# Pwr_entry.net
KiCad netlist of a schematic drawn in Altium Designer
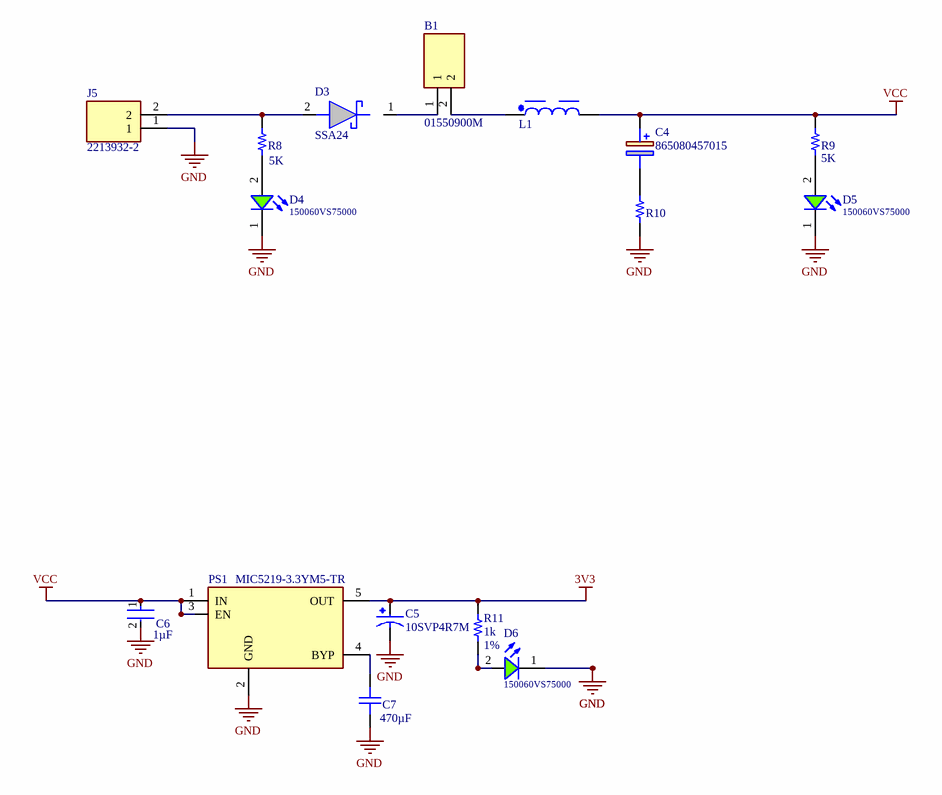
[diagram p0: Pwr_entry.SchDoc]

(export (version "E")
  (design (tool "Eeschema 10.0.6"))
  (components
    (comp (ref "B1")
      (value "01550900M")
      (footprint "01550900M")
      (description "Fuse Block 10 A 125V 1 Circuit Cartridge Surface Mount")
      (fields (field (name "MOUSER PART NUMBER") "576-01550900M"))
      (libsource (lib "01550900M") (part "01550900M"))
    )
    (comp (ref "C4")
      (value "865080457015")
      (footprint "CAPAE1030X1050L")
      (fields (field (name "MOUSER PART NUMBER") "710-865080457015"))
      (libsource (lib "865080457015") (part "865080457015"))
    )
    (comp (ref "C5")
      (value "10SVP4R7M")
      (footprint "CAP_10SVP4R7M")
      (libsource (lib "10SVP4R7M") (part "10SVP4R7M"))
    )
    (comp (ref "C6")
      (value "1µF")
      (footprint "FP-CL10-IPC_A")
      (fields (field (name "Comment") "GCG188L8EE105KA07D"))
      (libsource (lib "ILH") (part "02cd4be3c70576c341d710602a673aa"))
    )
    (comp (ref "C7")
      (value "470µF")
      (footprint "FP-CL10-IPC_B")
      (description "SMT Capacitor")
      (fields (field (name "Comment") "Capacitor"))
      (libsource (lib "ILH") (part "Capacitor"))
    )
    (comp (ref "D3")
      (value "SSA24")
      (footprint "DIOM5227X250N")
      (description "Schottky Diodes & Rectifiers 2A, 40V SMA SCHOTTKY")
      (libsource (lib "SSA24") (part "SSA24"))
    )
    (comp (ref "D4")
      (value "150060VS75000")
      (footprint "WL-SMCW_0603_H=0.7mm")
      (description "WL-SMCW SMT Mono-color Chip LED Waterclear, size 0603, Bright Green, 2V, 140deg")
      (fields (field (name "PUBLISHER") "Wurth Elektronik"))
      (libsource (lib "ILH") (part "Symbol"))
    )
    (comp (ref "D5")
      (value "150060VS75000")
      (footprint "WL-SMCW_0603_H=0.7mm")
      (description "WL-SMCW SMT Mono-color Chip LED Waterclear, size 0603, Bright Green, 2V, 140deg")
      (fields (field (name "PUBLISHER") "Wurth Elektronik"))
      (libsource (lib "ILH") (part "Symbol"))
    )
    (comp (ref "D6")
      (value "150060VS75000")
      (footprint "WL-SMCW_0603_H=0.7mm")
      (description "WL-SMCW SMT Mono-color Chip LED Waterclear, size 0603, Bright Green, 2V, 140deg")
      (fields (field (name "PUBLISHER") "Wurth Elektronik"))
      (libsource (lib "ILH") (part "Symbol"))
    )
    (comp (ref "J5")
      (value "2213932-2")
      (footprint "22139322")
      (description "Body Features: Product Orientation Right Angle")
      (fields (field (name "MOUSER PART NUMBER") "571-2213932-2"))
      (libsource (lib "2213932-2_CONN") (part "2213932-2"))
    )
    (comp (ref "L1")
      (value "47uH, 3.8A")
      (footprint "WE-PD_1210")
      (description "WE-PD SMT Power Inductor, size 1210, 47uH, 3.8A, 60mOhm")
      (fields
        (field (name "MANUFACTURER PART NUMBER") "7447709470")
        (field (name "MANUFACTURER") "Wurth Elektronik")
      )
      (libsource (lib "Altium_WE-PD_rev22g") (part "7447709470"))
    )
    (comp (ref "PS1")
      (value "MIC5219-3.3YM5-TR")
      (footprint "SOT95P280X145-5N")
      (fields (field (name "MOUSER PART NUMBER") "998-MIC5219-3.3YM5TR"))
      (libsource (lib "MIC5219-3.3YM5-TR") (part "MIC5219-3.3YM5-TR"))
    )
    (comp (ref "R8")
      (value "5K")
      (footprint "FP-CR0603-IPC_A")
      (fields
        (field (name "TOLERANCE") "5%")
        (field (name "POWER") "100mW")
        (field (name "JLCPCB PART #") "C913237")
      )
      (libsource (lib "ILH") (part "Resistor"))
    )
    (comp (ref "R9")
      (value "5K")
      (footprint "FP-CR0603-IPC_A")
      (fields
        (field (name "TOLERANCE") "5%")
        (field (name "POWER") "100mW")
        (field (name "JLCPCB PART #") "C913237")
      )
      (libsource (lib "ILH") (part "Resistor"))
    )
    (comp (ref "R10")
      (value "CRCW08050000Z0EA")
      (footprint "RESC2013X50X30ML20T20")
      (description "Fixed Resistor, Metal Glaze/thick Film, 0.125W, 0ohm, Surface Mount, 0805")
      (fields (field (name "POWER") "125mW"))
      (libsource (lib "ILH") (part "Resistor"))
    )
    (comp (ref "R11")
      (value "1k")
      (footprint "RESC1608X06N 0603 Medium Density")
      (description "RES SMD 1K OHM 1% 1/10W 0603")
      (fields
        (field (name "TOLERANCE") "1%")
        (field (name "JLCPCB PART #") "C21190")
        (field (name "POWER") "100mW")
      )
      (libsource (lib "ILH") (part "Resistor Tolerance"))
    )
  )
  (nets
    (net (code "1") (name "3V3") (class "Default")
      (node (ref "C5") (pin "1") (pinfunction "1_1") (pintype "passive"))
      (node (ref "PS1") (pin "5") (pinfunction "OUT_5") (pintype "passive"))
      (node (ref "R11") (pin "2") (pinfunction "2_2") (pintype "passive"))
    )
    (net (code "2") (name "GND") (class "Default")
      (node (ref "C5") (pin "2") (pinfunction "2_2") (pintype "passive"))
      (node (ref "C6") (pin "2") (pinfunction "2_2") (pintype "passive"))
      (node (ref "C7") (pin "1") (pinfunction "1_1") (pintype "passive"))
      (node (ref "D4") (pin "1") (pinfunction "K_1") (pintype "passive"))
      (node (ref "D5") (pin "1") (pinfunction "K_1") (pintype "passive"))
      (node (ref "D6") (pin "1") (pinfunction "K_1") (pintype "passive"))
      (node (ref "J5") (pin "1") (pinfunction "1_1") (pintype "passive"))
      (node (ref "PS1") (pin "2") (pinfunction "GND_2") (pintype "passive"))
      (node (ref "R10") (pin "1") (pinfunction "1_1") (pintype "passive"))
    )
    (net (code "3") (name "Net-(B1-Pad2)") (class "Default")
      (node (ref "B1") (pin "2") (pinfunction "2_2") (pintype "passive"))
      (node (ref "L1") (pin "1") (pinfunction "1_1") (pintype "passive"))
    )
    (net (code "4") (name "Net-(C4--)") (class "Default")
      (node (ref "C4") (pin "2") (pinfunction "-_2") (pintype "passive"))
      (node (ref "R10") (pin "2") (pinfunction "2_2") (pintype "passive"))
    )
    (net (code "5") (name "Net-(D3-A)") (class "Default")
      (node (ref "D3") (pin "2") (pinfunction "A_2") (pintype "passive"))
      (node (ref "J5") (pin "2") (pinfunction "2_2") (pintype "passive"))
      (node (ref "R8") (pin "2") (pinfunction "2_2") (pintype "passive"))
    )
    (net (code "6") (name "Net-(D3-K)") (class "Default")
      (node (ref "B1") (pin "1") (pinfunction "1_1") (pintype "passive"))
      (node (ref "D3") (pin "1") (pinfunction "K_1") (pintype "passive"))
    )
    (net (code "7") (name "Net-(D4-A)") (class "Default")
      (node (ref "D4") (pin "2") (pinfunction "A_2") (pintype "passive"))
      (node (ref "R8") (pin "1") (pinfunction "1_1") (pintype "passive"))
    )
    (net (code "8") (name "Net-(D5-A)") (class "Default")
      (node (ref "D5") (pin "2") (pinfunction "A_2") (pintype "passive"))
      (node (ref "R9") (pin "1") (pinfunction "1_1") (pintype "passive"))
    )
    (net (code "9") (name "Net-(D6-A)") (class "Default")
      (node (ref "D6") (pin "2") (pinfunction "A_2") (pintype "passive"))
      (node (ref "R11") (pin "1") (pinfunction "1_1") (pintype "passive"))
    )
    (net (code "10") (name "Net-(PS1-BYP)") (class "Default")
      (node (ref "C7") (pin "2") (pinfunction "2_2") (pintype "passive"))
      (node (ref "PS1") (pin "4") (pinfunction "BYP_4") (pintype "passive"))
    )
    (net (code "11") (name "VCC") (class "Default")
      (node (ref "C4") (pin "1") (pinfunction "+_1") (pintype "passive"))
      (node (ref "C6") (pin "1") (pinfunction "1_1") (pintype "passive"))
      (node (ref "L1") (pin "2") (pinfunction "2_2") (pintype "passive"))
      (node (ref "PS1") (pin "1") (pinfunction "IN_1") (pintype "passive"))
      (node (ref "PS1") (pin "3") (pinfunction "EN_3") (pintype "passive"))
      (node (ref "R9") (pin "2") (pinfunction "2_2") (pintype "passive"))
    )
  )
)
